# board2.net
KiCad netlist of a schematic drawn in EAGLE
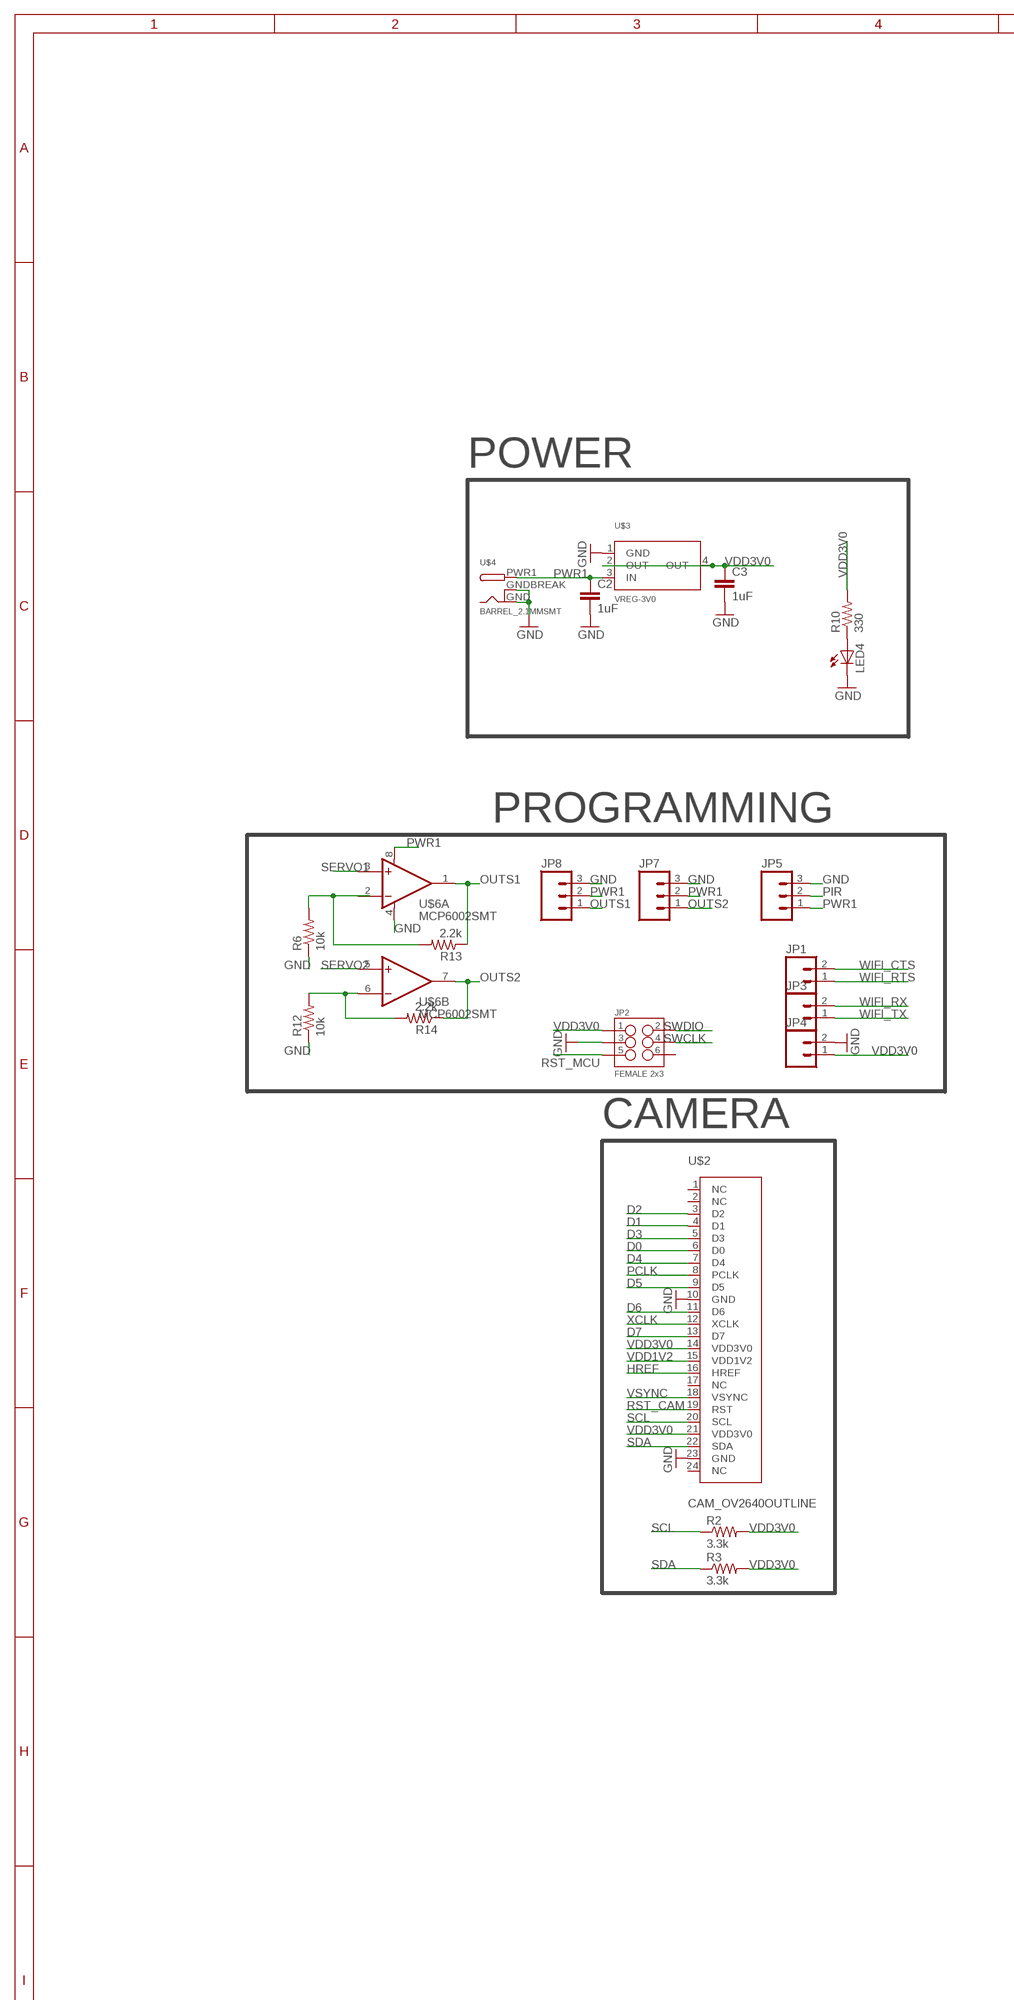
[diagram p0: schematic, sheet 1, part 1 of 2]
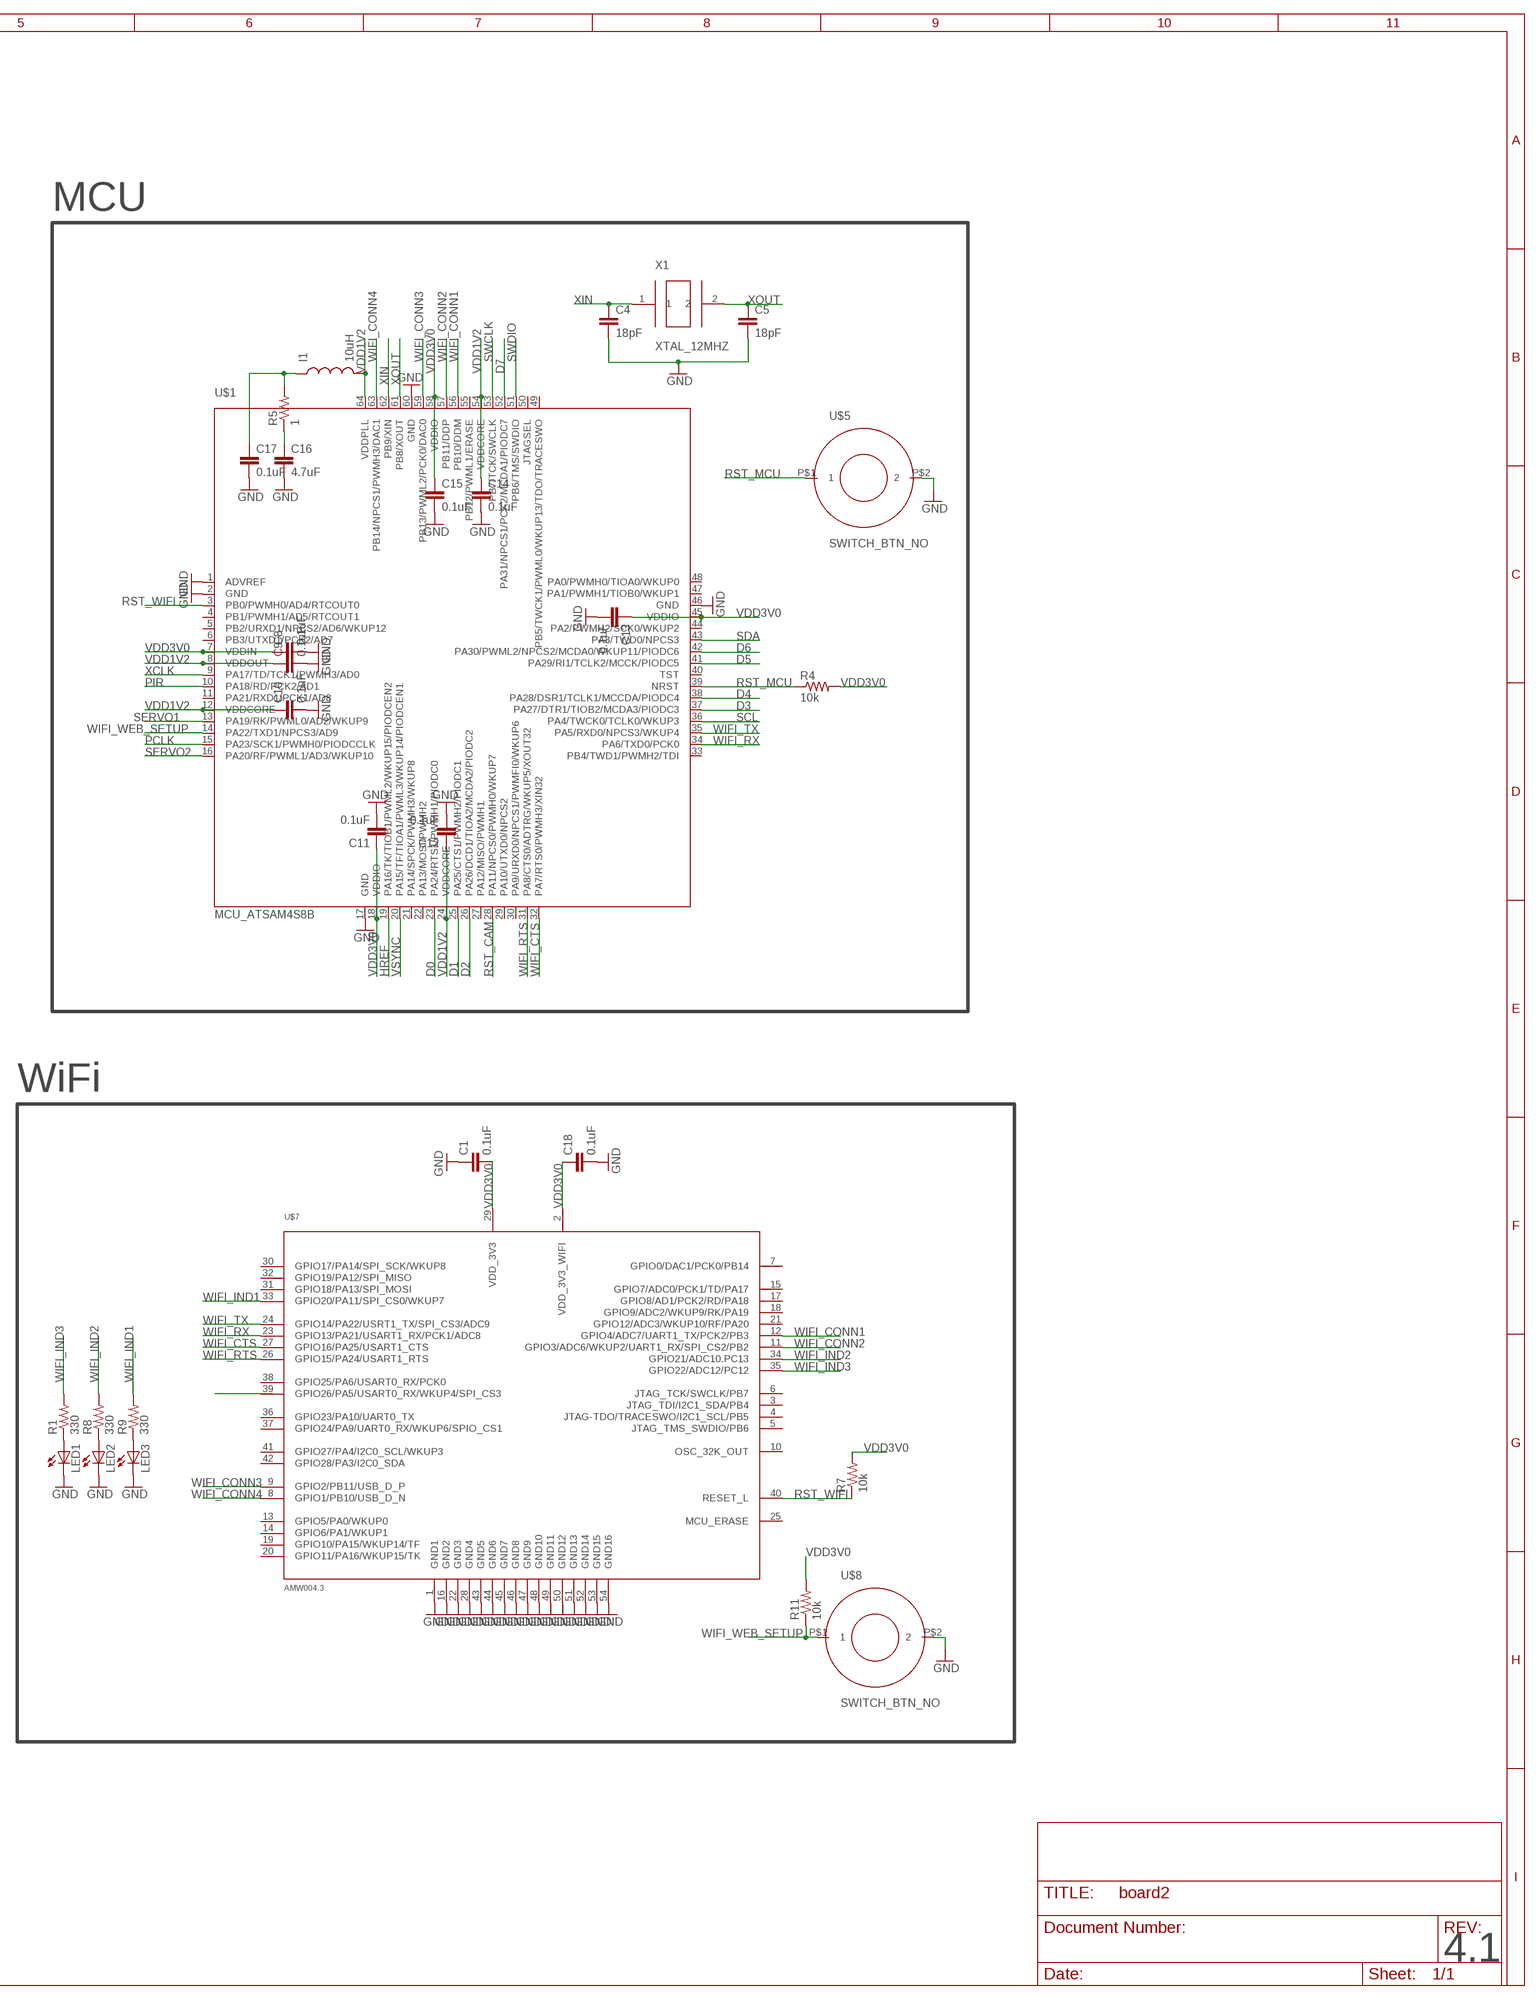
[diagram p1: schematic, sheet 1, part 2 of 2]

(export (version "E")
  (design (tool "Eeschema 10.0.6"))
  (components
    (comp (ref "C1")
      (value "0.1uF")
      (footprint "eagle-import:0805")
      (libsource (lib "eagle-import") (part "CAP"))
    )
    (comp (ref "C2")
      (value "1uF")
      (footprint "eagle-import:0805")
      (libsource (lib "eagle-import") (part "CAP"))
    )
    (comp (ref "C3")
      (value "1uF")
      (footprint "eagle-import:0805")
      (libsource (lib "eagle-import") (part "CAP"))
    )
    (comp (ref "C4")
      (value "18pF")
      (footprint "eagle-import:0805")
      (libsource (lib "eagle-import") (part "CAP"))
    )
    (comp (ref "C5")
      (value "18pF")
      (footprint "eagle-import:0805")
      (libsource (lib "eagle-import") (part "CAP"))
    )
    (comp (ref "C8")
      (value "0.1uF")
      (footprint "eagle-import:0805")
      (libsource (lib "eagle-import") (part "CAP"))
    )
    (comp (ref "C9")
      (value "0.1uF")
      (footprint "eagle-import:0805")
      (libsource (lib "eagle-import") (part "CAP"))
    )
    (comp (ref "C10")
      (value "0.1uF")
      (footprint "eagle-import:0805")
      (libsource (lib "eagle-import") (part "CAP"))
    )
    (comp (ref "C11")
      (value "0.1uF")
      (footprint "eagle-import:0805")
      (libsource (lib "eagle-import") (part "CAP"))
    )
    (comp (ref "C12")
      (value "0.1uF")
      (footprint "eagle-import:0805")
      (libsource (lib "eagle-import") (part "CAP"))
    )
    (comp (ref "C13")
      (value "0.1uF")
      (footprint "eagle-import:0805")
      (libsource (lib "eagle-import") (part "CAP"))
    )
    (comp (ref "C14")
      (value "0.1uF")
      (footprint "eagle-import:0805")
      (libsource (lib "eagle-import") (part "CAP"))
    )
    (comp (ref "C15")
      (value "0.1uF")
      (footprint "eagle-import:0805")
      (libsource (lib "eagle-import") (part "CAP"))
    )
    (comp (ref "C16")
      (value "4.7uF")
      (footprint "eagle-import:0805")
      (libsource (lib "eagle-import") (part "CAP"))
    )
    (comp (ref "C17")
      (value "0.1uF")
      (footprint "eagle-import:0805")
      (libsource (lib "eagle-import") (part "CAP"))
    )
    (comp (ref "C18")
      (value "0.1uF")
      (footprint "eagle-import:0805")
      (libsource (lib "eagle-import") (part "CAP"))
    )
    (comp (ref "I1")
      (value "10uH")
      (footprint "eagle-import:0805")
      (libsource (lib "eagle-import") (part "IND"))
    )
    (comp (ref "JP1")
      (value "M02PTH")
      (footprint "eagle-import:1X02")
      (libsource (lib "eagle-import") (part "M02PTH"))
    )
    (comp (ref "JP2")
      (value "FEMALE 2x3")
      (footprint "eagle-import:2X3")
      (libsource (lib "eagle-import") (part "M03X2FEMALE"))
    )
    (comp (ref "JP3")
      (value "M02PTH")
      (footprint "eagle-import:1X02")
      (libsource (lib "eagle-import") (part "M02PTH"))
    )
    (comp (ref "JP4")
      (value "M02PTH")
      (footprint "eagle-import:1X02")
      (libsource (lib "eagle-import") (part "M02PTH"))
    )
    (comp (ref "JP5")
      (value "M03LOCK")
      (footprint "eagle-import:1X03_LOCK")
      (libsource (lib "eagle-import") (part "M03LOCK"))
    )
    (comp (ref "JP7")
      (value "M03LOCK")
      (footprint "eagle-import:1X03_LOCK")
      (libsource (lib "eagle-import") (part "M03LOCK"))
    )
    (comp (ref "JP8")
      (value "M03LOCK")
      (footprint "eagle-import:1X03_LOCK")
      (libsource (lib "eagle-import") (part "M03LOCK"))
    )
    (comp (ref "LED1")
      (value "LED0603")
      (footprint "eagle-import:LED-0603")
      (libsource (lib "eagle-import") (part "LED0603"))
    )
    (comp (ref "LED2")
      (value "LED0603")
      (footprint "eagle-import:LED-0603")
      (libsource (lib "eagle-import") (part "LED0603"))
    )
    (comp (ref "LED3")
      (value "LED0603")
      (footprint "eagle-import:LED-0603")
      (libsource (lib "eagle-import") (part "LED0603"))
    )
    (comp (ref "LED4")
      (value "LED0603")
      (footprint "eagle-import:LED-0603")
      (libsource (lib "eagle-import") (part "LED0603"))
    )
    (comp (ref "R1")
      (value "330")
      (footprint "eagle-import:0805")
      (libsource (lib "eagle-import") (part "RES"))
    )
    (comp (ref "R2")
      (value "3.3k")
      (footprint "eagle-import:0805")
      (libsource (lib "eagle-import") (part "RES"))
    )
    (comp (ref "R3")
      (value "3.3k")
      (footprint "eagle-import:0805")
      (libsource (lib "eagle-import") (part "RES"))
    )
    (comp (ref "R4")
      (value "10k")
      (footprint "eagle-import:0805")
      (libsource (lib "eagle-import") (part "RES"))
    )
    (comp (ref "R5")
      (value "1")
      (footprint "eagle-import:0805")
      (libsource (lib "eagle-import") (part "RES"))
    )
    (comp (ref "R6")
      (value "10k")
      (footprint "eagle-import:0805")
      (libsource (lib "eagle-import") (part "RES"))
    )
    (comp (ref "R7")
      (value "10k")
      (footprint "eagle-import:0805")
      (libsource (lib "eagle-import") (part "RES"))
    )
    (comp (ref "R8")
      (value "330")
      (footprint "eagle-import:0805")
      (libsource (lib "eagle-import") (part "RES"))
    )
    (comp (ref "R9")
      (value "330")
      (footprint "eagle-import:0805")
      (libsource (lib "eagle-import") (part "RES"))
    )
    (comp (ref "R10")
      (value "330")
      (footprint "eagle-import:0805")
      (libsource (lib "eagle-import") (part "RES"))
    )
    (comp (ref "R11")
      (value "10k")
      (footprint "eagle-import:0805")
      (libsource (lib "eagle-import") (part "RES"))
    )
    (comp (ref "R12")
      (value "10k")
      (footprint "eagle-import:0805")
      (libsource (lib "eagle-import") (part "RES"))
    )
    (comp (ref "R13")
      (value "2.2k")
      (footprint "eagle-import:0805")
      (libsource (lib "eagle-import") (part "RES"))
    )
    (comp (ref "R14")
      (value "2.2k")
      (footprint "eagle-import:0805")
      (libsource (lib "eagle-import") (part "RES"))
    )
    (comp (ref "U$1")
      (value "MCU_ATSAM4S8B")
      (footprint "eagle-import:QFP50P1200X1200X160-64N")
      (libsource (lib "eagle-import") (part "MCU_ATSAM4S8B"))
    )
    (comp (ref "U$2")
      (value "CAM_OV2640OUTLINE")
      (footprint "eagle-import:CAM_CONN")
      (libsource (lib "eagle-import") (part "CAM_OV2640OUTLINE"))
    )
    (comp (ref "U$3")
      (value "VREG-3V0")
      (footprint "eagle-import:R-PDSO-G4_TI")
      (libsource (lib "eagle-import") (part "VREG-3V0"))
    )
    (comp (ref "U$4")
      (value "BARREL_2.1MMSMT")
      (footprint "eagle-import:DCJACK_2MM_SMT")
      (libsource (lib "eagle-import") (part "BARREL_2.1MMSMT"))
    )
    (comp (ref "U$5")
      (value "SWITCH_BTN_NO")
      (footprint "eagle-import:BTN_2")
      (libsource (lib "eagle-import") (part "SWITCH_BTN_NO"))
    )
    (comp (ref "U$6")
      (value "MCP6002SMT")
      (footprint "eagle-import:SOIC8")
      (libsource (lib "eagle-import") (part "MCP6002SMT"))
    )
    (comp (ref "U$7")
      (value "AMW004.3")
      (footprint "eagle-import:AMW004")
      (libsource (lib "eagle-import") (part "AMW004.3"))
    )
    (comp (ref "U$8")
      (value "SWITCH_BTN_NO")
      (footprint "eagle-import:BTN_2")
      (libsource (lib "eagle-import") (part "SWITCH_BTN_NO"))
    )
    (comp (ref "X1")
      (value "XTAL_12MHZ")
      (footprint "eagle-import:ABM7-16.000MHZ-D2Y-T")
      (libsource (lib "eagle-import") (part "XTAL_12MHZ"))
    )
  )
  (nets
    (net (code "1") (name "/D0") (class "Default")
      (node (ref "U$1") (pin "23") (pinfunction "PA24/RTS1/PWMH1/PIODC0_23") (pintype "bidirectional"))
      (node (ref "U$2") (pin "6") (pinfunction "D0_6") (pintype "bidirectional"))
    )
    (net (code "2") (name "/D1") (class "Default")
      (node (ref "U$1") (pin "25") (pinfunction "PA25/CTS1/PWMH2/PIODC1_25") (pintype "bidirectional"))
      (node (ref "U$2") (pin "4") (pinfunction "D1_4") (pintype "bidirectional"))
    )
    (net (code "3") (name "/D2") (class "Default")
      (node (ref "U$1") (pin "26") (pinfunction "PA26/DCD1/TIOA2/MCDA2/PIODC2_26") (pintype "bidirectional"))
      (node (ref "U$2") (pin "3") (pinfunction "D2_3") (pintype "bidirectional"))
    )
    (net (code "4") (name "/D3") (class "Default")
      (node (ref "U$1") (pin "37") (pinfunction "PA27/DTR1/TIOB2/MCDA3/PIODC3_37") (pintype "bidirectional"))
      (node (ref "U$2") (pin "5") (pinfunction "D3_5") (pintype "bidirectional"))
    )
    (net (code "5") (name "/D4") (class "Default")
      (node (ref "U$1") (pin "38") (pinfunction "PA28/DSR1/TCLK1/MCCDA/PIODC4_38") (pintype "bidirectional"))
      (node (ref "U$2") (pin "7") (pinfunction "D4_7") (pintype "bidirectional"))
    )
    (net (code "6") (name "/D5") (class "Default")
      (node (ref "U$1") (pin "41") (pinfunction "PA29/RI1/TCLK2/MCCK/PIODC5_41") (pintype "bidirectional"))
      (node (ref "U$2") (pin "9") (pinfunction "D5_9") (pintype "bidirectional"))
    )
    (net (code "7") (name "/D6") (class "Default")
      (node (ref "U$1") (pin "42") (pinfunction "PA30/PWML2/NPCS2/MCDA0/WKUP11/PIODC6_42") (pintype "bidirectional"))
      (node (ref "U$2") (pin "11") (pinfunction "D6_11") (pintype "bidirectional"))
    )
    (net (code "8") (name "/D7") (class "Default")
      (node (ref "U$1") (pin "52") (pinfunction "PA31/NPCS1/PCK2/MCDA1/PIODC7_52") (pintype "bidirectional"))
      (node (ref "U$2") (pin "13") (pinfunction "D7_13") (pintype "bidirectional"))
    )
    (net (code "9") (name "/HREF") (class "Default")
      (node (ref "U$1") (pin "19") (pinfunction "PA16/TK/TIOB1/PWML2/WKUP15/PIODCEN2_19") (pintype "bidirectional"))
      (node (ref "U$2") (pin "16") (pinfunction "HREF_16") (pintype "bidirectional"))
    )
    (net (code "10") (name "/OUTS1") (class "Default")
      (node (ref "JP8") (pin "1") (pinfunction "1_1") (pintype "passive"))
      (node (ref "R13") (pin "1") (pinfunction "1_1") (pintype "passive"))
      (node (ref "U$6") (pin "1") (pinfunction "OUT_1") (pintype "output"))
    )
    (net (code "11") (name "/OUTS2") (class "Default")
      (node (ref "JP7") (pin "1") (pinfunction "1_1") (pintype "passive"))
      (node (ref "R14") (pin "1") (pinfunction "1_1") (pintype "passive"))
      (node (ref "U$6") (pin "7") (pinfunction "OUT_7") (pintype "output"))
    )
    (net (code "12") (name "/PCLK") (class "Default")
      (node (ref "U$1") (pin "15") (pinfunction "PA23/SCK1/PWMH0/PIODCCLK_15") (pintype "bidirectional"))
      (node (ref "U$2") (pin "8") (pinfunction "PCLK_8") (pintype "bidirectional"))
    )
    (net (code "13") (name "/PIR") (class "Default")
      (node (ref "JP5") (pin "2") (pinfunction "2_2") (pintype "passive"))
      (node (ref "U$1") (pin "10") (pinfunction "PA18/RD/PCK2/AD1_10") (pintype "bidirectional"))
    )
    (net (code "14") (name "/PWR1") (class "Default")
      (node (ref "C2") (pin "1") (pinfunction "1_1") (pintype "passive"))
      (node (ref "JP5") (pin "1") (pinfunction "1_1") (pintype "passive"))
      (node (ref "JP7") (pin "2") (pinfunction "2_2") (pintype "passive"))
      (node (ref "JP8") (pin "2") (pinfunction "2_2") (pintype "passive"))
      (node (ref "U$3") (pin "3") (pinfunction "IN_3") (pintype "bidirectional"))
      (node (ref "U$4") (pin "PWR1") (pinfunction "PWR_PWR1") (pintype "power_in"))
      (node (ref "U$6") (pin "8") (pinfunction "V+_8") (pintype "power_in"))
    )
    (net (code "15") (name "/RST_CAM") (class "Default")
      (node (ref "U$1") (pin "28") (pinfunction "PA11/NPCS0/PWMH0/WKUP7_28") (pintype "bidirectional"))
      (node (ref "U$2") (pin "19") (pinfunction "RST_19") (pintype "bidirectional"))
    )
    (net (code "16") (name "/RST_MCU") (class "Default")
      (node (ref "JP2") (pin "5") (pinfunction "5_5") (pintype "bidirectional"))
      (node (ref "R4") (pin "1") (pinfunction "1_1") (pintype "passive"))
      (node (ref "U$1") (pin "39") (pinfunction "NRST_39") (pintype "bidirectional"))
      (node (ref "U$5") (pin "P$1") (pinfunction "1_P$1") (pintype "bidirectional"))
    )
    (net (code "17") (name "/RST_WIFI") (class "Default")
      (node (ref "R7") (pin "1") (pinfunction "1_1") (pintype "passive"))
      (node (ref "U$1") (pin "3") (pinfunction "PB0/PWMH0/AD4/RTCOUT0_3") (pintype "bidirectional"))
      (node (ref "U$7") (pin "40") (pinfunction "RESET_L_40") (pintype "bidirectional"))
    )
    (net (code "18") (name "/SCL") (class "Default")
      (node (ref "R2") (pin "1") (pinfunction "1_1") (pintype "passive"))
      (node (ref "U$1") (pin "36") (pinfunction "PA4/TWCK0/TCLK0/WKUP3_36") (pintype "bidirectional"))
      (node (ref "U$2") (pin "20") (pinfunction "SCL_20") (pintype "bidirectional"))
    )
    (net (code "19") (name "/SDA") (class "Default")
      (node (ref "R3") (pin "1") (pinfunction "1_1") (pintype "passive"))
      (node (ref "U$1") (pin "43") (pinfunction "PA3/TWD0/NPCS3_43") (pintype "bidirectional"))
      (node (ref "U$2") (pin "22") (pinfunction "SDA_22") (pintype "bidirectional"))
    )
    (net (code "20") (name "/SERVO1") (class "Default")
      (node (ref "U$1") (pin "13") (pinfunction "PA19/RK/PWML0/AD2/WKUP9_13") (pintype "bidirectional"))
      (node (ref "U$6") (pin "3") (pinfunction "+IN_3") (pintype "input"))
    )
    (net (code "21") (name "/SERVO2") (class "Default")
      (node (ref "U$1") (pin "16") (pinfunction "PA20/RF/PWML1/AD3/WKUP10_16") (pintype "bidirectional"))
      (node (ref "U$6") (pin "5") (pinfunction "+IN_5") (pintype "input"))
    )
    (net (code "22") (name "/SWCLK") (class "Default")
      (node (ref "JP2") (pin "4") (pinfunction "4_4") (pintype "bidirectional"))
      (node (ref "U$1") (pin "53") (pinfunction "PB7/TCK/SWCLK_53") (pintype "bidirectional"))
    )
    (net (code "23") (name "/SWDIO") (class "Default")
      (node (ref "JP2") (pin "2") (pinfunction "2_2") (pintype "bidirectional"))
      (node (ref "U$1") (pin "51") (pinfunction "PB6/TMS/SWDIO_51") (pintype "bidirectional"))
    )
    (net (code "24") (name "/VDD1V2") (class "Default")
      (node (ref "C10") (pin "1") (pinfunction "1_1") (pintype "passive"))
      (node (ref "C12") (pin "1") (pinfunction "1_1") (pintype "passive"))
      (node (ref "C14") (pin "1") (pinfunction "1_1") (pintype "passive"))
      (node (ref "C9") (pin "1") (pinfunction "1_1") (pintype "passive"))
      (node (ref "I1") (pin "2") (pinfunction "2_2") (pintype "passive"))
      (node (ref "U$1") (pin "12") (pinfunction "VDDCORE_12") (pintype "bidirectional"))
      (node (ref "U$1") (pin "24") (pinfunction "VDDCORE_24") (pintype "bidirectional"))
      (node (ref "U$1") (pin "54") (pinfunction "VDDCORE_54") (pintype "bidirectional"))
      (node (ref "U$1") (pin "64") (pinfunction "VDDPLL_64") (pintype "bidirectional"))
      (node (ref "U$1") (pin "8") (pinfunction "VDDOUT_8") (pintype "bidirectional"))
      (node (ref "U$2") (pin "15") (pinfunction "VDD1V2_15") (pintype "bidirectional"))
    )
    (net (code "25") (name "/VDD3V0") (class "Default")
      (node (ref "C1") (pin "2") (pinfunction "2_2") (pintype "passive"))
      (node (ref "C11") (pin "1") (pinfunction "1_1") (pintype "passive"))
      (node (ref "C13") (pin "1") (pinfunction "1_1") (pintype "passive"))
      (node (ref "C15") (pin "1") (pinfunction "1_1") (pintype "passive"))
      (node (ref "C18") (pin "1") (pinfunction "1_1") (pintype "passive"))
      (node (ref "C3") (pin "1") (pinfunction "1_1") (pintype "passive"))
      (node (ref "C8") (pin "1") (pinfunction "1_1") (pintype "passive"))
      (node (ref "JP2") (pin "1") (pinfunction "1_1") (pintype "bidirectional"))
      (node (ref "JP4") (pin "1") (pinfunction "1_1") (pintype "passive"))
      (node (ref "R10") (pin "2") (pinfunction "2_2") (pintype "passive"))
      (node (ref "R11") (pin "2") (pinfunction "2_2") (pintype "passive"))
      (node (ref "R2") (pin "2") (pinfunction "2_2") (pintype "passive"))
      (node (ref "R3") (pin "2") (pinfunction "2_2") (pintype "passive"))
      (node (ref "R4") (pin "2") (pinfunction "2_2") (pintype "passive"))
      (node (ref "R7") (pin "2") (pinfunction "2_2") (pintype "passive"))
      (node (ref "U$1") (pin "18") (pinfunction "VDDIO_18") (pintype "bidirectional"))
      (node (ref "U$1") (pin "45") (pinfunction "VDDIO_45") (pintype "bidirectional"))
      (node (ref "U$1") (pin "58") (pinfunction "VDDIO_58") (pintype "bidirectional"))
      (node (ref "U$1") (pin "7") (pinfunction "VDDIN_7") (pintype "bidirectional"))
      (node (ref "U$2") (pin "14") (pinfunction "VDD3V0_14") (pintype "bidirectional"))
      (node (ref "U$2") (pin "21") (pinfunction "VDD3V0_21") (pintype "bidirectional"))
      (node (ref "U$3") (pin "2") (pinfunction "OUT_2") (pintype "bidirectional"))
      (node (ref "U$3") (pin "4") (pinfunction "OUT_4") (pintype "bidirectional"))
      (node (ref "U$7") (pin "2") (pinfunction "VDD_3V3_WIFI_2") (pintype "bidirectional"))
      (node (ref "U$7") (pin "29") (pinfunction "VDD_3V3_29") (pintype "bidirectional"))
    )
    (net (code "26") (name "/VSYNC") (class "Default")
      (node (ref "U$1") (pin "20") (pinfunction "PA15/TF/TIOA1/PWML3/WKUP14/PIODCEN1_20") (pintype "bidirectional"))
      (node (ref "U$2") (pin "18") (pinfunction "VSYNC_18") (pintype "bidirectional"))
    )
    (net (code "27") (name "/WIFI_CONN1") (class "Default")
      (node (ref "U$1") (pin "56") (pinfunction "PB10/DDM_56") (pintype "bidirectional"))
      (node (ref "U$7") (pin "12") (pinfunction "GPIO4/ADC7/UART1_TX/PCK2/PB3_12") (pintype "bidirectional"))
    )
    (net (code "28") (name "/WIFI_CONN2") (class "Default")
      (node (ref "U$1") (pin "57") (pinfunction "PB11/DDP_57") (pintype "bidirectional"))
      (node (ref "U$7") (pin "11") (pinfunction "GPIO3/ADC6/WKUP2/UART1_RX/SPI_CS2/PB2_11") (pintype "bidirectional"))
    )
    (net (code "29") (name "/WIFI_CONN3") (class "Default")
      (node (ref "U$1") (pin "59") (pinfunction "PB13/PWML2/PCK0/DAC0_59") (pintype "bidirectional"))
      (node (ref "U$7") (pin "9") (pinfunction "GPIO2/PB11/USB_D_P_9") (pintype "bidirectional"))
    )
    (net (code "30") (name "/WIFI_CONN4") (class "Default")
      (node (ref "U$1") (pin "63") (pinfunction "PB14/NPCS1/PWMH3/DAC1_63") (pintype "bidirectional"))
      (node (ref "U$7") (pin "8") (pinfunction "GPIO1/PB10/USB_D_N_8") (pintype "bidirectional"))
    )
    (net (code "31") (name "/WIFI_CTS") (class "Default")
      (node (ref "JP1") (pin "2") (pinfunction "2_2") (pintype "passive"))
      (node (ref "U$1") (pin "32") (pinfunction "PA7/RTS0/PWMH3/XIN32_32") (pintype "bidirectional"))
      (node (ref "U$7") (pin "27") (pinfunction "GPIO16/PA25/USART1_CTS_27") (pintype "bidirectional"))
    )
    (net (code "32") (name "/WIFI_IND1") (class "Default")
      (node (ref "R9") (pin "2") (pinfunction "2_2") (pintype "passive"))
      (node (ref "U$7") (pin "33") (pinfunction "GPIO20/PA11/SPI_CS0/WKUP7_33") (pintype "bidirectional"))
    )
    (net (code "33") (name "/WIFI_IND2") (class "Default")
      (node (ref "R8") (pin "2") (pinfunction "2_2") (pintype "passive"))
      (node (ref "U$7") (pin "34") (pinfunction "GPIO21/ADC10.PC13_34") (pintype "bidirectional"))
    )
    (net (code "34") (name "/WIFI_IND3") (class "Default")
      (node (ref "R1") (pin "2") (pinfunction "2_2") (pintype "passive"))
      (node (ref "U$7") (pin "35") (pinfunction "GPIO22/ADC12/PC12_35") (pintype "bidirectional"))
    )
    (net (code "35") (name "/WIFI_RTS") (class "Default")
      (node (ref "JP1") (pin "1") (pinfunction "1_1") (pintype "passive"))
      (node (ref "U$1") (pin "31") (pinfunction "PA8/CTS0/ADTRG/WKUP5/XOUT32_31") (pintype "bidirectional"))
      (node (ref "U$7") (pin "26") (pinfunction "GPIO15/PA24/USART1_RTS_26") (pintype "bidirectional"))
    )
    (net (code "36") (name "/WIFI_RX") (class "Default")
      (node (ref "JP3") (pin "2") (pinfunction "2_2") (pintype "passive"))
      (node (ref "U$1") (pin "34") (pinfunction "PA6/TXD0/PCK0_34") (pintype "bidirectional"))
      (node (ref "U$7") (pin "23") (pinfunction "GPIO13/PA21/USART1_RX/PCK1/ADC8_23") (pintype "bidirectional"))
    )
    (net (code "37") (name "/WIFI_TX") (class "Default")
      (node (ref "JP3") (pin "1") (pinfunction "1_1") (pintype "passive"))
      (node (ref "U$1") (pin "35") (pinfunction "PA5/RXD0/NPCS3/WKUP4_35") (pintype "bidirectional"))
      (node (ref "U$7") (pin "24") (pinfunction "GPIO14/PA22/USRT1_TX/SPI_CS3/ADC9_24") (pintype "bidirectional"))
    )
    (net (code "38") (name "/WIFI_WEB_SETUP") (class "Default")
      (node (ref "R11") (pin "1") (pinfunction "1_1") (pintype "passive"))
      (node (ref "U$1") (pin "14") (pinfunction "PA22/TXD1/NPCS3/AD9_14") (pintype "bidirectional"))
      (node (ref "U$8") (pin "P$1") (pinfunction "1_P$1") (pintype "bidirectional"))
    )
    (net (code "39") (name "/XCLK") (class "Default")
      (node (ref "U$1") (pin "9") (pinfunction "PA17/TD/TCK1/PWMH3/AD0_9") (pintype "bidirectional"))
      (node (ref "U$2") (pin "12") (pinfunction "XCLK_12") (pintype "bidirectional"))
    )
    (net (code "40") (name "/XIN") (class "Default")
      (node (ref "C4") (pin "1") (pinfunction "1_1") (pintype "passive"))
      (node (ref "U$1") (pin "62") (pinfunction "PB9/XIN_62") (pintype "bidirectional"))
      (node (ref "X1") (pin "1") (pinfunction "1_1") (pintype "bidirectional"))
    )
    (net (code "41") (name "/XOUT") (class "Default")
      (node (ref "C5") (pin "1") (pinfunction "1_1") (pintype "passive"))
      (node (ref "U$1") (pin "61") (pinfunction "PB8/XOUT_61") (pintype "bidirectional"))
      (node (ref "X1") (pin "2") (pinfunction "2_2") (pintype "bidirectional"))
    )
    (net (code "42") (name "GND") (class "Default")
      (node (ref "C1") (pin "1") (pinfunction "1_1") (pintype "passive"))
      (node (ref "C10") (pin "2") (pinfunction "2_2") (pintype "passive"))
      (node (ref "C11") (pin "2") (pinfunction "2_2") (pintype "passive"))
      (node (ref "C12") (pin "2") (pinfunction "2_2") (pintype "passive"))
      (node (ref "C13") (pin "2") (pinfunction "2_2") (pintype "passive"))
      (node (ref "C14") (pin "2") (pinfunction "2_2") (pintype "passive"))
      (node (ref "C15") (pin "2") (pinfunction "2_2") (pintype "passive"))
      (node (ref "C16") (pin "2") (pinfunction "2_2") (pintype "passive"))
      (node (ref "C17") (pin "2") (pinfunction "2_2") (pintype "passive"))
      (node (ref "C18") (pin "2") (pinfunction "2_2") (pintype "passive"))
      (node (ref "C2") (pin "2") (pinfunction "2_2") (pintype "passive"))
      (node (ref "C3") (pin "2") (pinfunction "2_2") (pintype "passive"))
      (node (ref "C4") (pin "2") (pinfunction "2_2") (pintype "passive"))
      (node (ref "C5") (pin "2") (pinfunction "2_2") (pintype "passive"))
      (node (ref "C8") (pin "2") (pinfunction "2_2") (pintype "passive"))
      (node (ref "C9") (pin "2") (pinfunction "2_2") (pintype "passive"))
      (node (ref "JP2") (pin "3") (pinfunction "3_3") (pintype "bidirectional"))
      (node (ref "JP4") (pin "2") (pinfunction "2_2") (pintype "passive"))
      (node (ref "JP5") (pin "3") (pinfunction "3_3") (pintype "passive"))
      (node (ref "JP7") (pin "3") (pinfunction "3_3") (pintype "passive"))
      (node (ref "JP8") (pin "3") (pinfunction "3_3") (pintype "passive"))
      (node (ref "LED1") (pin "C") (pinfunction "C_C") (pintype "passive"))
      (node (ref "LED2") (pin "C") (pinfunction "C_C") (pintype "passive"))
      (node (ref "LED3") (pin "C") (pinfunction "C_C") (pintype "passive"))
      (node (ref "LED4") (pin "C") (pinfunction "C_C") (pintype "passive"))
      (node (ref "R12") (pin "1") (pinfunction "1_1") (pintype "passive"))
      (node (ref "R6") (pin "1") (pinfunction "1_1") (pintype "passive"))
      (node (ref "U$1") (pin "1") (pinfunction "ADVREF_1") (pintype "bidirectional"))
      (node (ref "U$1") (pin "17") (pinfunction "GND_17") (pintype "bidirectional"))
      (node (ref "U$1") (pin "2") (pinfunction "GND_2") (pintype "bidirectional"))
      (node (ref "U$1") (pin "46") (pinfunction "GND_46") (pintype "bidirectional"))
      (node (ref "U$1") (pin "60") (pinfunction "GND_60") (pintype "bidirectional"))
      (node (ref "U$2") (pin "10") (pinfunction "GND_10") (pintype "bidirectional"))
      (node (ref "U$2") (pin "23") (pinfunction "GND_23") (pintype "bidirectional"))
      (node (ref "U$3") (pin "1") (pinfunction "GND_1") (pintype "bidirectional"))
      (node (ref "U$4") (pin "GND") (pinfunction "GND_GND") (pintype "power_in"))
      (node (ref "U$4") (pin "GNDBREAK") (pinfunction "GNDBREAK_GNDBREAK") (pintype "power_in"))
      (node (ref "U$5") (pin "P$2") (pinfunction "2_P$2") (pintype "bidirectional"))
      (node (ref "U$6") (pin "4") (pinfunction "V-_4") (pintype "power_in"))
      (node (ref "U$7") (pin "1") (pinfunction "GND1_1") (pintype "power_in"))
      (node (ref "U$7") (pin "16") (pinfunction "GND2_16") (pintype "power_in"))
      (node (ref "U$7") (pin "22") (pinfunction "GND3_22") (pintype "power_in"))
      (node (ref "U$7") (pin "28") (pinfunction "GND4_28") (pintype "power_in"))
      (node (ref "U$7") (pin "43") (pinfunction "GND5_43") (pintype "power_in"))
      (node (ref "U$7") (pin "44") (pinfunction "GND6_44") (pintype "power_in"))
      (node (ref "U$7") (pin "45") (pinfunction "GND7_45") (pintype "power_in"))
      (node (ref "U$7") (pin "46") (pinfunction "GND8_46") (pintype "power_in"))
      (node (ref "U$7") (pin "47") (pinfunction "GND9_47") (pintype "power_in"))
      (node (ref "U$7") (pin "48") (pinfunction "GND10_48") (pintype "power_in"))
      (node (ref "U$7") (pin "49") (pinfunction "GND11_49") (pintype "power_in"))
      (node (ref "U$7") (pin "50") (pinfunction "GND12_50") (pintype "power_in"))
      (node (ref "U$7") (pin "51") (pinfunction "GND13_51") (pintype "power_in"))
      (node (ref "U$7") (pin "52") (pinfunction "GND14_52") (pintype "power_in"))
      (node (ref "U$7") (pin "53") (pinfunction "GND15_53") (pintype "power_in"))
      (node (ref "U$7") (pin "54") (pinfunction "GND16_54") (pintype "power_in"))
      (node (ref "U$8") (pin "P$2") (pinfunction "2_P$2") (pintype "bidirectional"))
    )
    (net (code "43") (name "Net-(C16-Pad1)") (class "Default")
      (node (ref "C16") (pin "1") (pinfunction "1_1") (pintype "passive"))
      (node (ref "R5") (pin "1") (pinfunction "1_1") (pintype "passive"))
    )
    (net (code "44") (name "Net-(C17-Pad1)") (class "Default")
      (node (ref "C17") (pin "1") (pinfunction "1_1") (pintype "passive"))
      (node (ref "I1") (pin "1") (pinfunction "1_1") (pintype "passive"))
      (node (ref "R5") (pin "2") (pinfunction "2_2") (pintype "passive"))
    )
    (net (code "45") (name "Net-(LED1-PadA)") (class "Default")
      (node (ref "LED1") (pin "A") (pinfunction "A_A") (pintype "passive"))
      (node (ref "R1") (pin "1") (pinfunction "1_1") (pintype "passive"))
    )
    (net (code "46") (name "Net-(LED2-PadA)") (class "Default")
      (node (ref "LED2") (pin "A") (pinfunction "A_A") (pintype "passive"))
      (node (ref "R8") (pin "1") (pinfunction "1_1") (pintype "passive"))
    )
    (net (code "47") (name "Net-(LED3-PadA)") (class "Default")
      (node (ref "LED3") (pin "A") (pinfunction "A_A") (pintype "passive"))
      (node (ref "R9") (pin "1") (pinfunction "1_1") (pintype "passive"))
    )
    (net (code "48") (name "Net-(LED4-PadA)") (class "Default")
      (node (ref "LED4") (pin "A") (pinfunction "A_A") (pintype "passive"))
      (node (ref "R10") (pin "1") (pinfunction "1_1") (pintype "passive"))
    )
    (net (code "49") (name "Net-(R13-Pad2)") (class "Default")
      (node (ref "R13") (pin "2") (pinfunction "2_2") (pintype "passive"))
      (node (ref "R6") (pin "2") (pinfunction "2_2") (pintype "passive"))
    )
    (net (code "50") (name "Net-(U$6B--IN)") (class "Default")
      (node (ref "R12") (pin "2") (pinfunction "2_2") (pintype "passive"))
      (node (ref "R14") (pin "2") (pinfunction "2_2") (pintype "passive"))
      (node (ref "U$6") (pin "6") (pinfunction "-IN_6") (pintype "input"))
    )
    (net (code "51") (name "unconnected-(JP2-Pad6)") (class "Default")
      (node (ref "JP2") (pin "6") (pinfunction "6_6") (pintype "bidirectional"))
    )
    (net (code "52") (name "unconnected-(U$1-JTAGSEL-Pad50)") (class "Default")
      (node (ref "U$1") (pin "50") (pinfunction "JTAGSEL_50") (pintype "bidirectional"))
    )
    (net (code "53") (name "unconnected-(U$1-PA0{slash}PWMH0{slash}TIOA0{slash}WKUP0-Pad48)") (class "Default")
      (node (ref "U$1") (pin "48") (pinfunction "PA0/PWMH0/TIOA0/WKUP0_48") (pintype "bidirectional"))
    )
    (net (code "54") (name "unconnected-(U$1-PA1{slash}PWMH1{slash}TIOB0{slash}WKUP1-Pad47)") (class "Default")
      (node (ref "U$1") (pin "47") (pinfunction "PA1/PWMH1/TIOB0/WKUP1_47") (pintype "bidirectional"))
    )
    (net (code "55") (name "unconnected-(U$1-PA2{slash}PWMH2{slash}SCK0{slash}WKUP2-Pad44)") (class "Default")
      (node (ref "U$1") (pin "44") (pinfunction "PA2/PWMH2/SCK0/WKUP2_44") (pintype "bidirectional"))
    )
    (net (code "56") (name "unconnected-(U$1-PA9{slash}URXD0{slash}NPCS1{slash}PWMFI0{slash}WKUP6-Pad30)") (class "Default")
      (node (ref "U$1") (pin "30") (pinfunction "PA9/URXD0/NPCS1/PWMFI0/WKUP6_30") (pintype "bidirectional"))
    )
    (net (code "57") (name "unconnected-(U$1-PA10{slash}UTXD0{slash}NPCS2-Pad29)") (class "Default")
      (node (ref "U$1") (pin "29") (pinfunction "PA10/UTXD0/NPCS2_29") (pintype "bidirectional"))
    )
    (net (code "58") (name "unconnected-(U$1-PA12{slash}MISO{slash}PWMH1-Pad27)") (class "Default")
      (node (ref "U$1") (pin "27") (pinfunction "PA12/MISO/PWMH1_27") (pintype "bidirectional"))
    )
    (net (code "59") (name "unconnected-(U$1-PA13{slash}MOSI{slash}PWMH2-Pad22)") (class "Default")
      (node (ref "U$1") (pin "22") (pinfunction "PA13/MOSI/PWMH2_22") (pintype "bidirectional"))
    )
    (net (code "60") (name "unconnected-(U$1-PA14{slash}SPCK{slash}PWMH3{slash}WKUP8-Pad21)") (class "Default")
      (node (ref "U$1") (pin "21") (pinfunction "PA14/SPCK/PWMH3/WKUP8_21") (pintype "bidirectional"))
    )
    (net (code "61") (name "unconnected-(U$1-PA21{slash}RXD1{slash}PCK1{slash}AD8-Pad11)") (class "Default")
      (node (ref "U$1") (pin "11") (pinfunction "PA21/RXD1/PCK1/AD8_11") (pintype "bidirectional"))
    )
    (net (code "62") (name "unconnected-(U$1-PB1{slash}PWMH1{slash}AD5{slash}RTCOUT1-Pad4)") (class "Default")
      (node (ref "U$1") (pin "4") (pinfunction "PB1/PWMH1/AD5/RTCOUT1_4") (pintype "bidirectional"))
    )
    (net (code "63") (name "unconnected-(U$1-PB2{slash}URXD1{slash}NPCS2{slash}AD6{slash}WKUP12-Pad5)") (class "Default")
      (node (ref "U$1") (pin "5") (pinfunction "PB2/URXD1/NPCS2/AD6/WKUP12_5") (pintype "bidirectional"))
    )
    (net (code "64") (name "unconnected-(U$1-PB3{slash}UTXD1{slash}PCK2{slash}AD7-Pad6)") (class "Default")
      (node (ref "U$1") (pin "6") (pinfunction "PB3/UTXD1/PCK2/AD7_6") (pintype "bidirectional"))
    )
    (net (code "65") (name "unconnected-(U$1-PB4{slash}TWD1{slash}PWMH2{slash}TDI-Pad33)") (class "Default")
      (node (ref "U$1") (pin "33") (pinfunction "PB4/TWD1/PWMH2/TDI_33") (pintype "bidirectional"))
    )
    (net (code "66") (name "unconnected-(U$1-PB5{slash}TWCK1{slash}PWML0{slash}WKUP13{slash}TDO{slash}TRACESWO-Pad49)") (class "Default")
      (node (ref "U$1") (pin "49") (pinfunction "PB5/TWCK1/PWML0/WKUP13/TDO/TRACESWO_49") (pintype "bidirectional"))
    )
    (net (code "67") (name "unconnected-(U$1-PB12{slash}PWML1{slash}ERASE-Pad55)") (class "Default")
      (node (ref "U$1") (pin "55") (pinfunction "PB12/PWML1/ERASE_55") (pintype "bidirectional"))
    )
    (net (code "68") (name "unconnected-(U$1-TST-Pad40)") (class "Default")
      (node (ref "U$1") (pin "40") (pinfunction "TST_40") (pintype "bidirectional"))
    )
    (net (code "69") (name "unconnected-(U$2-NC-Pad1)") (class "Default")
      (node (ref "U$2") (pin "1") (pinfunction "NC_1") (pintype "bidirectional"))
    )
    (net (code "70") (name "unconnected-(U$2-NC-Pad2)") (class "Default")
      (node (ref "U$2") (pin "2") (pinfunction "NC_2") (pintype "bidirectional"))
    )
    (net (code "71") (name "unconnected-(U$2-NC-Pad17)") (class "Default")
      (node (ref "U$2") (pin "17") (pinfunction "NC_17") (pintype "bidirectional"))
    )
    (net (code "72") (name "unconnected-(U$2-NC-Pad24)") (class "Default")
      (node (ref "U$2") (pin "24") (pinfunction "NC_24") (pintype "bidirectional"))
    )
    (net (code "73") (name "unconnected-(U$6A--IN-Pad2)") (class "Default")
      (node (ref "U$6") (pin "2") (pinfunction "-IN_2") (pintype "input"))
    )
    (net (code "74") (name "unconnected-(U$7-GPIO0{slash}DAC1{slash}PCK0{slash}PB14-Pad7)") (class "Default")
      (node (ref "U$7") (pin "7") (pinfunction "GPIO0/DAC1/PCK0/PB14_7") (pintype "bidirectional"))
    )
    (net (code "75") (name "unconnected-(U$7-GPIO5{slash}PA0{slash}WKUP0-Pad13)") (class "Default")
      (node (ref "U$7") (pin "13") (pinfunction "GPIO5/PA0/WKUP0_13") (pintype "bidirectional"))
    )
    (net (code "76") (name "unconnected-(U$7-GPIO6{slash}PA1{slash}WKUP1-Pad14)") (class "Default")
      (node (ref "U$7") (pin "14") (pinfunction "GPIO6/PA1/WKUP1_14") (pintype "bidirectional"))
    )
    (net (code "77") (name "unconnected-(U$7-GPIO7{slash}ADC0{slash}PCK1{slash}TD{slash}PA17-Pad15)") (class "Default")
      (node (ref "U$7") (pin "15") (pinfunction "GPIO7/ADC0/PCK1/TD/PA17_15") (pintype "bidirectional"))
    )
    (net (code "78") (name "unconnected-(U$7-GPIO8{slash}AD1{slash}PCK2{slash}RD{slash}PA18-Pad17)") (class "Default")
      (node (ref "U$7") (pin "17") (pinfunction "GPIO8/AD1/PCK2/RD/PA18_17") (pintype "bidirectional"))
    )
    (net (code "79") (name "unconnected-(U$7-GPIO9{slash}ADC2{slash}WKUP9{slash}RK{slash}PA19-Pad18)") (class "Default")
      (node (ref "U$7") (pin "18") (pinfunction "GPIO9/ADC2/WKUP9/RK/PA19_18") (pintype "bidirectional"))
    )
    (net (code "80") (name "unconnected-(U$7-GPIO10{slash}PA15{slash}WKUP14{slash}TF-Pad19)") (class "Default")
      (node (ref "U$7") (pin "19") (pinfunction "GPIO10/PA15/WKUP14/TF_19") (pintype "bidirectional"))
    )
    (net (code "81") (name "unconnected-(U$7-GPIO11{slash}PA16{slash}WKUP15{slash}TK-Pad20)") (class "Default")
      (node (ref "U$7") (pin "20") (pinfunction "GPIO11/PA16/WKUP15/TK_20") (pintype "bidirectional"))
    )
    (net (code "82") (name "unconnected-(U$7-GPIO12{slash}ADC3{slash}WKUP10{slash}RF{slash}PA20-Pad21)") (class "Default")
      (node (ref "U$7") (pin "21") (pinfunction "GPIO12/ADC3/WKUP10/RF/PA20_21") (pintype "bidirectional"))
    )
    (net (code "83") (name "unconnected-(U$7-GPIO17{slash}PA14{slash}SPI_SCK{slash}WKUP8-Pad30)") (class "Default")
      (node (ref "U$7") (pin "30") (pinfunction "GPIO17/PA14/SPI_SCK/WKUP8_30") (pintype "bidirectional"))
    )
    (net (code "84") (name "unconnected-(U$7-GPIO18{slash}PA13{slash}SPI_MOSI-Pad31)") (class "Default")
      (node (ref "U$7") (pin "31") (pinfunction "GPIO18/PA13/SPI_MOSI_31") (pintype "bidirectional"))
    )
    (net (code "85") (name "unconnected-(U$7-GPIO19{slash}PA12{slash}SPI_MISO-Pad32)") (class "Default")
      (node (ref "U$7") (pin "32") (pinfunction "GPIO19/PA12/SPI_MISO_32") (pintype "bidirectional"))
    )
    (net (code "86") (name "unconnected-(U$7-GPIO23{slash}PA10{slash}UART0_TX-Pad36)") (class "Default")
      (node (ref "U$7") (pin "36") (pinfunction "GPIO23/PA10/UART0_TX_36") (pintype "bidirectional"))
    )
    (net (code "87") (name "unconnected-(U$7-GPIO24{slash}PA9{slash}UART0_RX{slash}WKUP6{slash}SPIO_CS1-Pad37)") (class "Default")
      (node (ref "U$7") (pin "37") (pinfunction "GPIO24/PA9/UART0_RX/WKUP6/SPIO_CS1_37") (pintype "bidirectional"))
    )
    (net (code "88") (name "unconnected-(U$7-GPIO25{slash}PA6{slash}USART0_RX{slash}PCK0-Pad38)") (class "Default")
      (node (ref "U$7") (pin "38") (pinfunction "GPIO25/PA6/USART0_RX/PCK0_38") (pintype "bidirectional"))
    )
    (net (code "89") (name "unconnected-(U$7-GPIO26{slash}PA5{slash}USART0_RX{slash}WKUP4{slash}SPI_CS3-Pad39)") (class "Default")
      (node (ref "U$7") (pin "39") (pinfunction "GPIO26/PA5/USART0_RX/WKUP4/SPI_CS3_39") (pintype "bidirectional"))
    )
    (net (code "90") (name "unconnected-(U$7-GPIO27{slash}PA4{slash}I2C0_SCL{slash}WKUP3-Pad41)") (class "Default")
      (node (ref "U$7") (pin "41") (pinfunction "GPIO27/PA4/I2C0_SCL/WKUP3_41") (pintype "bidirectional"))
    )
    (net (code "91") (name "unconnected-(U$7-GPIO28{slash}PA3{slash}I2C0_SDA-Pad42)") (class "Default")
      (node (ref "U$7") (pin "42") (pinfunction "GPIO28/PA3/I2C0_SDA_42") (pintype "bidirectional"))
    )
    (net (code "92") (name "unconnected-(U$7-JTAG-TDO{slash}TRACESWO{slash}I2C1_SCL{slash}PB5-Pad4)") (class "Default")
      (node (ref "U$7") (pin "4") (pinfunction "JTAG-TDO/TRACESWO/I2C1_SCL/PB5_4") (pintype "bidirectional"))
    )
    (net (code "93") (name "unconnected-(U$7-JTAG_TCK{slash}SWCLK{slash}PB7-Pad6)") (class "Default")
      (node (ref "U$7") (pin "6") (pinfunction "JTAG_TCK/SWCLK/PB7_6") (pintype "bidirectional"))
    )
    (net (code "94") (name "unconnected-(U$7-JTAG_TDI{slash}I2C1_SDA{slash}PB4-Pad3)") (class "Default")
      (node (ref "U$7") (pin "3") (pinfunction "JTAG_TDI/I2C1_SDA/PB4_3") (pintype "bidirectional"))
    )
    (net (code "95") (name "unconnected-(U$7-JTAG_TMS_SWDIO{slash}PB6-Pad5)") (class "Default")
      (node (ref "U$7") (pin "5") (pinfunction "JTAG_TMS_SWDIO/PB6_5") (pintype "bidirectional"))
    )
    (net (code "96") (name "unconnected-(U$7-MCU_ERASE-Pad25)") (class "Default")
      (node (ref "U$7") (pin "25") (pinfunction "MCU_ERASE_25") (pintype "input"))
    )
    (net (code "97") (name "unconnected-(U$7-OSC_32K_OUT-Pad10)") (class "Default")
      (node (ref "U$7") (pin "10") (pinfunction "OSC_32K_OUT_10") (pintype "output"))
    )
  )
)
